# RTU_LMG_RTC.net
KiCad netlist of a schematic drawn in Altium Designer
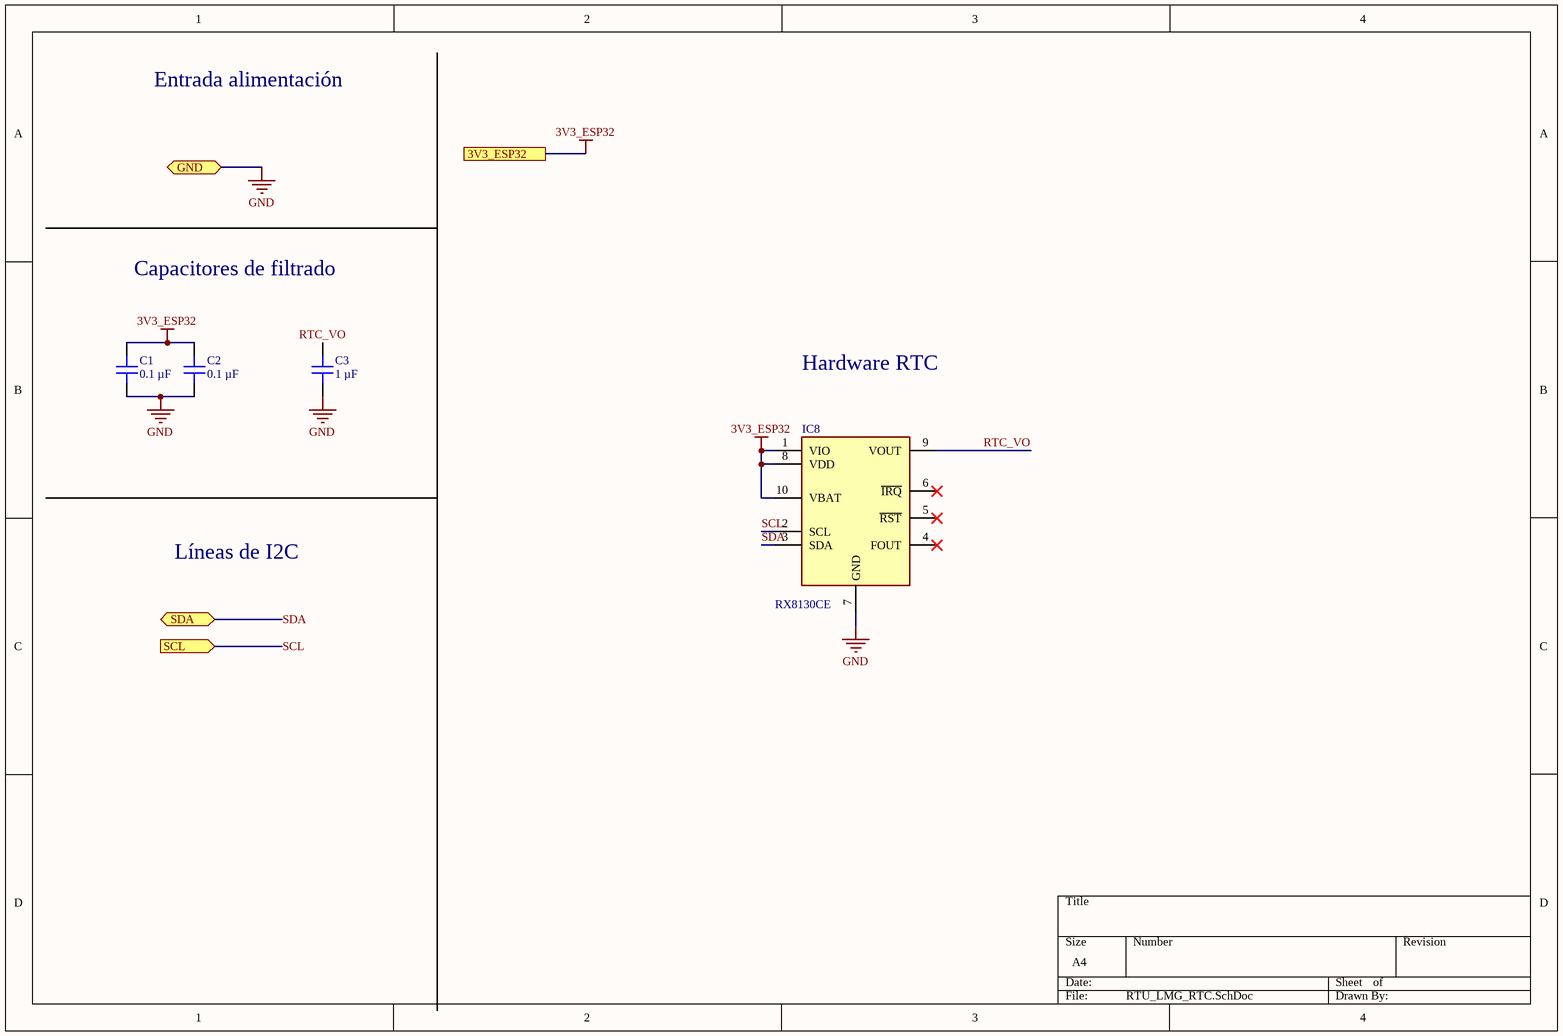
[diagram p0: RTU_LMG_RTC.SchDoc]

(export (version "E")
  (design (tool "Eeschema 10.0.6"))
  (components
    (comp (ref "C1")
      (value "0.1 µF")
      (footprint "MURATA GRM155 0402_1005")
      (description "CAP CER 0.1UF 50V X7R 0402")
      (fields
        (field (name "PART NUMBER") "GRM155R71H104KE14D")
        (field (name "MANUFACTURER") "Murata Electronics")
      )
      (libsource (lib "Celestial Altium Library - altium_library") (part "Capacitor"))
    )
    (comp (ref "C2")
      (value "0.1 µF")
      (footprint "MURATA GRM155 0402_1005")
      (description "CAP CER 0.1UF 50V X7R 0402")
      (fields
        (field (name "PART NUMBER") "GRM155R71H104KE14D")
        (field (name "MANUFACTURER") "Murata Electronics")
      )
      (libsource (lib "Celestial Altium Library - altium_library") (part "Capacitor"))
    )
    (comp (ref "C3")
      (value "1 µF")
      (footprint "CAP 0402_1005")
      (description "CAP CER 1UF 16V X5R 0402")
      (fields
        (field (name "PART NUMBER") "CL05A105KO5NNNC")
        (field (name "MANUFACTURER") "Samsung Electro-Mechanics")
      )
      (libsource (lib "Celestial Altium Library - altium_library") (part "Capacitor"))
    )
    (comp (ref "IC8")
      (value "RX8130CE")
      (footprint "DIN_DC_Base_Board_components_PCB_footprints:RX8130CE")
      (description "IC RTC CLK/CALENDAR I2C 10SMD")
      (libsource (lib "DIN_DC_Base_Board_components_SCH_footprints") (part "RX8130CE"))
    )
  )
  (nets
    (net (code "1") (name "/RTC_VO") (class "Default")
      (node (ref "C3") (pin "1") (pinfunction "1_1") (pintype "passive"))
      (node (ref "IC8") (pin "9") (pinfunction "VOUT_9") (pintype "passive"))
    )
    (net (code "2") (name "/SCL") (class "Default")
      (node (ref "IC8") (pin "2") (pinfunction "SCL_2") (pintype "passive"))
    )
    (net (code "3") (name "/SDA") (class "Default")
      (node (ref "IC8") (pin "3") (pinfunction "SDA_3") (pintype "passive"))
    )
    (net (code "4") (name "3V3_ESP32") (class "Default")
      (node (ref "C1") (pin "1") (pinfunction "1_1") (pintype "passive"))
      (node (ref "C2") (pin "1") (pinfunction "1_1") (pintype "passive"))
      (node (ref "IC8") (pin "1") (pinfunction "VIO_1") (pintype "passive"))
      (node (ref "IC8") (pin "10") (pinfunction "VBAT_10") (pintype "passive"))
      (node (ref "IC8") (pin "8") (pinfunction "VDD_8") (pintype "passive"))
    )
    (net (code "5") (name "GND") (class "Default")
      (node (ref "C1") (pin "2") (pinfunction "2_2") (pintype "passive"))
      (node (ref "C2") (pin "2") (pinfunction "2_2") (pintype "passive"))
      (node (ref "C3") (pin "2") (pinfunction "2_2") (pintype "passive"))
      (node (ref "IC8") (pin "7") (pinfunction "GND_7") (pintype "passive"))
    )
    (net (code "6") (name "unconnected-(IC8-FOUT-Pad4)") (class "Default")
      (node (ref "IC8") (pin "4") (pinfunction "FOUT_4") (pintype "passive+no_connect"))
    )
    (net (code "7") (name "unconnected-(IC8-~{IRQ}-Pad6)") (class "Default")
      (node (ref "IC8") (pin "6") (pinfunction "~{IRQ}_6") (pintype "passive+no_connect"))
    )
    (net (code "8") (name "unconnected-(IC8-~{RST}-Pad5)") (class "Default")
      (node (ref "IC8") (pin "5") (pinfunction "~{RST}_5") (pintype "passive+no_connect"))
    )
  )
)
